# breakout.net
KiCad netlist of a schematic drawn in EAGLE
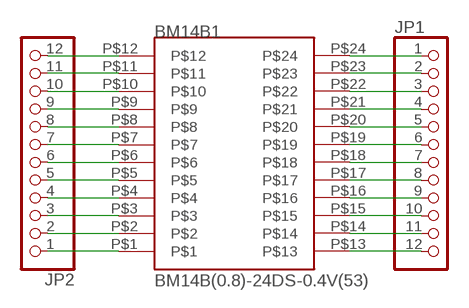
[diagram p0: schematic, sheet 1]

(export (version "E")
  (design (tool "Eeschema 10.0.6"))
  (components
    (comp (ref "BM14B1")
      (value "BM14B(0.8)-24DS-0.4V(53)")
      (footprint "eagle-import:BM14B(0.8)-24DS-0.4V(53)")
      (libsource (lib "eagle-import") (part "BM14B(0.8)-24DS-0.4V(53)"))
    )
    (comp (ref "JP1")
      (value "PINHD-1X12")
      (footprint "eagle-import:1X12")
      (libsource (lib "eagle-import") (part "PINHD-1X12"))
    )
    (comp (ref "JP2")
      (value "PINHD-1X12")
      (footprint "eagle-import:1X12")
      (libsource (lib "eagle-import") (part "PINHD-1X12"))
    )
  )
  (nets
    (net (code "1") (name "Net-(BM14B1-PadP$1)") (class "Default")
      (node (ref "BM14B1") (pin "P$1") (pinfunction "P$1_P$1") (pintype "bidirectional"))
      (node (ref "JP2") (pin "1") (pinfunction "1_1") (pintype "passive"))
    )
    (net (code "2") (name "Net-(BM14B1-PadP$2)") (class "Default")
      (node (ref "BM14B1") (pin "P$2") (pinfunction "P$2_P$2") (pintype "bidirectional"))
      (node (ref "JP2") (pin "2") (pinfunction "2_2") (pintype "passive"))
    )
    (net (code "3") (name "Net-(BM14B1-PadP$3)") (class "Default")
      (node (ref "BM14B1") (pin "P$3") (pinfunction "P$3_P$3") (pintype "bidirectional"))
      (node (ref "JP2") (pin "3") (pinfunction "3_3") (pintype "passive"))
    )
    (net (code "4") (name "Net-(BM14B1-PadP$4)") (class "Default")
      (node (ref "BM14B1") (pin "P$4") (pinfunction "P$4_P$4") (pintype "bidirectional"))
      (node (ref "JP2") (pin "4") (pinfunction "4_4") (pintype "passive"))
    )
    (net (code "5") (name "Net-(BM14B1-PadP$5)") (class "Default")
      (node (ref "BM14B1") (pin "P$5") (pinfunction "P$5_P$5") (pintype "bidirectional"))
      (node (ref "JP2") (pin "5") (pinfunction "5_5") (pintype "passive"))
    )
    (net (code "6") (name "Net-(BM14B1-PadP$6)") (class "Default")
      (node (ref "BM14B1") (pin "P$6") (pinfunction "P$6_P$6") (pintype "bidirectional"))
      (node (ref "JP2") (pin "6") (pinfunction "6_6") (pintype "passive"))
    )
    (net (code "7") (name "Net-(BM14B1-PadP$7)") (class "Default")
      (node (ref "BM14B1") (pin "P$7") (pinfunction "P$7_P$7") (pintype "bidirectional"))
      (node (ref "JP2") (pin "7") (pinfunction "7_7") (pintype "passive"))
    )
    (net (code "8") (name "Net-(BM14B1-PadP$8)") (class "Default")
      (node (ref "BM14B1") (pin "P$8") (pinfunction "P$8_P$8") (pintype "bidirectional"))
      (node (ref "JP2") (pin "8") (pinfunction "8_8") (pintype "passive"))
    )
    (net (code "9") (name "Net-(BM14B1-PadP$9)") (class "Default")
      (node (ref "BM14B1") (pin "P$9") (pinfunction "P$9_P$9") (pintype "bidirectional"))
      (node (ref "JP2") (pin "9") (pinfunction "9_9") (pintype "passive"))
    )
    (net (code "10") (name "Net-(BM14B1-PadP$10)") (class "Default")
      (node (ref "BM14B1") (pin "P$10") (pinfunction "P$10_P$10") (pintype "bidirectional"))
      (node (ref "JP2") (pin "10") (pinfunction "10_10") (pintype "passive"))
    )
    (net (code "11") (name "Net-(BM14B1-PadP$11)") (class "Default")
      (node (ref "BM14B1") (pin "P$11") (pinfunction "P$11_P$11") (pintype "bidirectional"))
      (node (ref "JP2") (pin "11") (pinfunction "11_11") (pintype "passive"))
    )
    (net (code "12") (name "Net-(BM14B1-PadP$12)") (class "Default")
      (node (ref "BM14B1") (pin "P$12") (pinfunction "P$12_P$12") (pintype "bidirectional"))
      (node (ref "JP2") (pin "12") (pinfunction "12_12") (pintype "passive"))
    )
    (net (code "13") (name "Net-(BM14B1-PadP$13)") (class "Default")
      (node (ref "BM14B1") (pin "P$13") (pinfunction "P$13_P$13") (pintype "bidirectional"))
      (node (ref "JP1") (pin "12") (pinfunction "12_12") (pintype "passive"))
    )
    (net (code "14") (name "Net-(BM14B1-PadP$14)") (class "Default")
      (node (ref "BM14B1") (pin "P$14") (pinfunction "P$14_P$14") (pintype "bidirectional"))
      (node (ref "JP1") (pin "11") (pinfunction "11_11") (pintype "passive"))
    )
    (net (code "15") (name "Net-(BM14B1-PadP$15)") (class "Default")
      (node (ref "BM14B1") (pin "P$15") (pinfunction "P$15_P$15") (pintype "bidirectional"))
      (node (ref "JP1") (pin "10") (pinfunction "10_10") (pintype "passive"))
    )
    (net (code "16") (name "Net-(BM14B1-PadP$16)") (class "Default")
      (node (ref "BM14B1") (pin "P$16") (pinfunction "P$16_P$16") (pintype "bidirectional"))
      (node (ref "JP1") (pin "9") (pinfunction "9_9") (pintype "passive"))
    )
    (net (code "17") (name "Net-(BM14B1-PadP$17)") (class "Default")
      (node (ref "BM14B1") (pin "P$17") (pinfunction "P$17_P$17") (pintype "bidirectional"))
      (node (ref "JP1") (pin "8") (pinfunction "8_8") (pintype "passive"))
    )
    (net (code "18") (name "Net-(BM14B1-PadP$18)") (class "Default")
      (node (ref "BM14B1") (pin "P$18") (pinfunction "P$18_P$18") (pintype "bidirectional"))
      (node (ref "JP1") (pin "7") (pinfunction "7_7") (pintype "passive"))
    )
    (net (code "19") (name "Net-(BM14B1-PadP$19)") (class "Default")
      (node (ref "BM14B1") (pin "P$19") (pinfunction "P$19_P$19") (pintype "bidirectional"))
      (node (ref "JP1") (pin "6") (pinfunction "6_6") (pintype "passive"))
    )
    (net (code "20") (name "Net-(BM14B1-PadP$20)") (class "Default")
      (node (ref "BM14B1") (pin "P$20") (pinfunction "P$20_P$20") (pintype "bidirectional"))
      (node (ref "JP1") (pin "5") (pinfunction "5_5") (pintype "passive"))
    )
    (net (code "21") (name "Net-(BM14B1-PadP$21)") (class "Default")
      (node (ref "BM14B1") (pin "P$21") (pinfunction "P$21_P$21") (pintype "bidirectional"))
      (node (ref "JP1") (pin "4") (pinfunction "4_4") (pintype "passive"))
    )
    (net (code "22") (name "Net-(BM14B1-PadP$22)") (class "Default")
      (node (ref "BM14B1") (pin "P$22") (pinfunction "P$22_P$22") (pintype "bidirectional"))
      (node (ref "JP1") (pin "3") (pinfunction "3_3") (pintype "passive"))
    )
    (net (code "23") (name "Net-(BM14B1-PadP$23)") (class "Default")
      (node (ref "BM14B1") (pin "P$23") (pinfunction "P$23_P$23") (pintype "bidirectional"))
      (node (ref "JP1") (pin "2") (pinfunction "2_2") (pintype "passive"))
    )
    (net (code "24") (name "Net-(BM14B1-PadP$24)") (class "Default")
      (node (ref "BM14B1") (pin "P$24") (pinfunction "P$24_P$24") (pintype "bidirectional"))
      (node (ref "JP1") (pin "1") (pinfunction "1_1") (pintype "passive"))
    )
  )
)
